# Microcontroleur_Affichage.net
KiCad netlist of a schematic drawn in Altium Designer
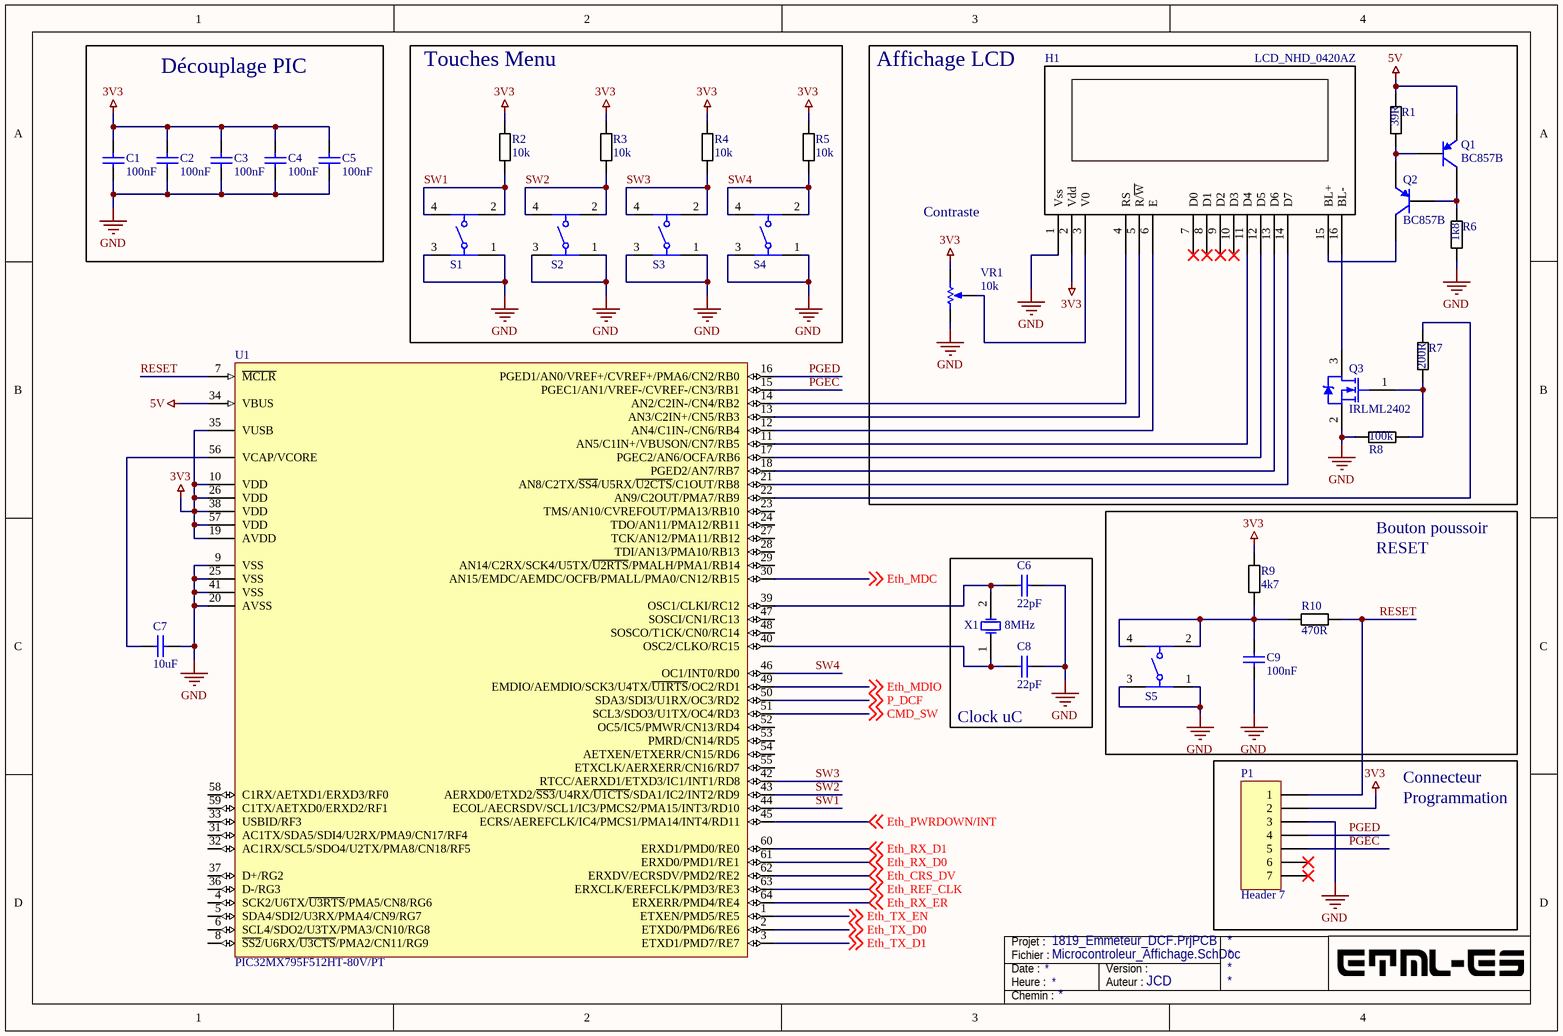
[diagram p0: Microcontroleur_Affichage.SchDoc]

(export (version "E")
  (design (tool "Eeschema 10.0.6"))
  (components
    (comp (ref "C1")
      (value "100nF")
      (footprint "C0805")
      (description "Capacitor")
      (fields (field (name "PUBLISHER") "Altium Limited"))
      (libsource (lib "Miscellaneous Devices") (part "Cap"))
    )
    (comp (ref "C2")
      (value "100nF")
      (footprint "C0805")
      (description "Capacitor")
      (fields (field (name "PUBLISHER") "Altium Limited"))
      (libsource (lib "Miscellaneous Devices") (part "Cap"))
    )
    (comp (ref "C3")
      (value "100nF")
      (footprint "C0805")
      (description "Capacitor")
      (fields (field (name "PUBLISHER") "Altium Limited"))
      (libsource (lib "Miscellaneous Devices") (part "Cap"))
    )
    (comp (ref "C4")
      (value "100nF")
      (footprint "C0805")
      (description "Capacitor")
      (fields (field (name "PUBLISHER") "Altium Limited"))
      (libsource (lib "Miscellaneous Devices") (part "Cap"))
    )
    (comp (ref "C5")
      (value "100nF")
      (footprint "C0805")
      (description "Capacitor")
      (fields (field (name "PUBLISHER") "Altium Limited"))
      (libsource (lib "Miscellaneous Devices") (part "Cap"))
    )
    (comp (ref "C6")
      (value "22pF")
      (footprint "C0805")
      (description "Capacitor")
      (fields (field (name "PUBLISHER") "Altium Limited"))
      (libsource (lib "Miscellaneous Devices") (part "Cap"))
    )
    (comp (ref "C7")
      (value "10uF")
      (footprint "C0805")
      (description "Capacitor")
      (fields (field (name "PUBLISHER") "Altium Limited"))
      (libsource (lib "Miscellaneous Devices") (part "Cap"))
    )
    (comp (ref "C8")
      (value "22pF")
      (footprint "C0805")
      (description "Capacitor")
      (fields (field (name "PUBLISHER") "Altium Limited"))
      (libsource (lib "Miscellaneous Devices") (part "Cap"))
    )
    (comp (ref "C9")
      (value "100nF")
      (footprint "C0805")
      (description "Capacitor")
      (fields (field (name "PUBLISHER") "Altium Limited"))
      (libsource (lib "Miscellaneous Devices") (part "Cap"))
    )
    (comp (ref "H1")
      (value "LCD_NHD_0420AZ")
      (footprint "NHD-0420AZ-FSW-GBW-33V3")
      (libsource (lib "LibComposant1819") (part "NHD-0420AZ-FSW-GBW-33V3"))
    )
    (comp (ref "P1")
      (value "Header 7")
      (footprint "HDR1X7")
      (description "Header, 7-Pin")
      (fields (field (name "PUBLISHER") "Altium Limited"))
      (libsource (lib "Miscellaneous Connectors") (part "Header 7"))
    )
    (comp (ref "Q1")
      (value "BC857B")
      (footprint "INF-SOT23_L")
      (description "PNP Silicon AF Transistor, 45 V VCEO, 100 mA IC, SOT23, Reel, Green")
      (fields (field (name "MANUFACTURER") "Infineon"))
      (libsource (lib "Altium Content Vault") (part "INF-BJTPNP-BEC-3"))
    )
    (comp (ref "Q2")
      (value "BC857B")
      (footprint "INF-SOT23_L")
      (description "PNP Silicon AF Transistor, 45 V VCEO, 100 mA IC, SOT23, Reel, Green")
      (fields (field (name "MANUFACTURER") "Infineon"))
      (libsource (lib "Altium Content Vault") (part "INF-BJTPNP-BEC-3"))
    )
    (comp (ref "Q3")
      (value "IRLML2402")
      (footprint "INTR-IRLML2402TRPBF-3_V")
      (description "HEXFET(R) Power MOSFET, N-Channel, 20 V, 1.2 A, 3-Pin SOT-23, RoHS, Tape and Reel")
      (fields (field (name "MANUFACTURER") "International Rectifier"))
      (libsource (lib "Altium Content Vault") (part "NEMOS-GSD-3_A"))
    )
    (comp (ref "R1") (value "39R") (footprint "RESC0805(2012)_L") (libsource (lib "") (part "Resistance_1")))
    (comp (ref "R2") (value "10k") (footprint "RESC0805(2012)_L") (libsource (lib "") (part "Resistance_2")))
    (comp (ref "R3") (value "10k") (footprint "RESC0805(2012)_L") (libsource (lib "") (part "Resistance_2")))
    (comp (ref "R4") (value "10k") (footprint "RESC0805(2012)_L") (libsource (lib "") (part "Resistance_2")))
    (comp (ref "R5") (value "10k") (footprint "RESC0805(2012)_L") (libsource (lib "") (part "Resistance_2")))
    (comp (ref "R6") (value "1k8") (footprint "RESC0805(2012)_L") (libsource (lib "") (part "Resistance_1")))
    (comp (ref "R7") (value "200R") (footprint "RESC0805(2012)_L") (libsource (lib "") (part "Resistance_1")))
    (comp (ref "R8")
      (value "100k")
      (footprint "RESC0805(2012)_L")
      (libsource (lib "LibComposant1819") (part "Resistance"))
    )
    (comp (ref "R9") (value "4k7") (footprint "RESC0805(2012)_L") (libsource (lib "") (part "Resistance_2")))
    (comp (ref "R10")
      (value "470R")
      (footprint "RESC0805(2012)_L")
      (libsource (lib "LibComposant1819") (part "Resistance"))
    )
    (comp (ref "S1")
      (value "430152095836")
      (footprint "430152095836")
      (description "6x6mm SMD Tact Switch WS-TASV, height 9.5 mm, 360 gf")
      (fields (field (name "PUBLISHER") "Wurth Elektronik"))
      (libsource (lib "ALTIUM-WS-TASV-rev17b") (part "430152095836"))
    )
    (comp (ref "S2")
      (value "430152095836")
      (footprint "430152095836")
      (description "6x6mm SMD Tact Switch WS-TASV, height 9.5 mm, 360 gf")
      (fields (field (name "PUBLISHER") "Wurth Elektronik"))
      (libsource (lib "ALTIUM-WS-TASV-rev17b") (part "430152095836"))
    )
    (comp (ref "S3")
      (value "430152095836")
      (footprint "430152095836")
      (description "6x6mm SMD Tact Switch WS-TASV, height 9.5 mm, 360 gf")
      (fields (field (name "PUBLISHER") "Wurth Elektronik"))
      (libsource (lib "ALTIUM-WS-TASV-rev17b") (part "430152095836"))
    )
    (comp (ref "S4")
      (value "430152095836")
      (footprint "430152095836")
      (description "6x6mm SMD Tact Switch WS-TASV, height 9.5 mm, 360 gf")
      (fields (field (name "PUBLISHER") "Wurth Elektronik"))
      (libsource (lib "ALTIUM-WS-TASV-rev17b") (part "430152095836"))
    )
    (comp (ref "S5")
      (value "430152043836")
      (footprint "430152043836")
      (description "6x6mm SMD Tact Switch WS-TASV, height 4.3 mm, 360 gf")
      (fields (field (name "PUBLISHER") "Wurth Elektronik"))
      (libsource (lib "ALTIUM-WS-TASV-rev17b") (part "430152043836"))
    )
    (comp (ref "U1")
      (value "PIC32MX795F512HT-80V/PT")
      (footprint "TQFP-PT64_L")
      (libsource (lib "Altium Content Vault") (part "MC-32B-MX795-SQ64"))
    )
    (comp (ref "VR1")
      (value "10k")
      (footprint "BOUR-3362P")
      (description "Square Trimpot(R) Trimming Potentiometer, 10 KOhm, 300 V, -55 to 125 degC, 3-Pin THD, RoHS, Tube")
      (fields (field (name "TOLERANCE") "1%"))
      (libsource (lib "Altium Content Vault") (part "RES-POT-3"))
    )
    (comp (ref "X1")
      (value "8MHz")
      (footprint "ECS-80-18-5PX-TR_V")
      (description "Low Profile Quartz Crystal, 8.0 MHz, 2-Pin SMD, RoHS, Tape and Reel")
      (fields (field (name "TOLERANCE") "30PPM") (field (name "MANUFACTURER") "ECS"))
      (libsource (lib "Altium Content Vault") (part "XTAL_1-2-2"))
    )
  )
  (nets
    (net (code "1") (name "/PGEC") (class "Default")
      (node (ref "P1") (pin "5") (pinfunction "5_5") (pintype "passive"))
      (node (ref "U1") (pin "15") (pinfunction "PGEC1/AN1/VREF-/CVREF-/CN3/RB1_15") (pintype "bidirectional"))
    )
    (net (code "2") (name "/PGED") (class "Default")
      (node (ref "P1") (pin "4") (pinfunction "4_4") (pintype "passive"))
      (node (ref "U1") (pin "16") (pinfunction "PGED1/AN0/VREF+/CVREF+/PMA6/CN2/RB0_16") (pintype "bidirectional"))
    )
    (net (code "3") (name "/RESET") (class "Default")
      (node (ref "P1") (pin "1") (pinfunction "1_1") (pintype "passive"))
      (node (ref "R10") (pin "2") (pinfunction "2_2") (pintype "passive"))
      (node (ref "U1") (pin "7") (pinfunction "~{MCLR}_7") (pintype "input"))
    )
    (net (code "4") (name "/SW1") (class "Default")
      (node (ref "R2") (pin "2") (pinfunction "2_2") (pintype "passive"))
      (node (ref "S1") (pin "2") (pinfunction "2_2") (pintype "passive"))
      (node (ref "S1") (pin "4") (pinfunction "4_4") (pintype "passive"))
      (node (ref "U1") (pin "44") (pinfunction "ECOL/AECRSDV/SCL1/IC3/PMCS2/PMA15/INT3/RD10_44") (pintype "bidirectional"))
    )
    (net (code "5") (name "/SW2") (class "Default")
      (node (ref "R3") (pin "2") (pinfunction "2_2") (pintype "passive"))
      (node (ref "S2") (pin "2") (pinfunction "2_2") (pintype "passive"))
      (node (ref "S2") (pin "4") (pinfunction "4_4") (pintype "passive"))
      (node (ref "U1") (pin "43") (pinfunction "AERXD0/ETXD2/~{SS3}/U4RX/~{U1CTS}/SDA1/IC2/INT2/RD9_43") (pintype "bidirectional"))
    )
    (net (code "6") (name "/SW3") (class "Default")
      (node (ref "R4") (pin "2") (pinfunction "2_2") (pintype "passive"))
      (node (ref "S3") (pin "2") (pinfunction "2_2") (pintype "passive"))
      (node (ref "S3") (pin "4") (pinfunction "4_4") (pintype "passive"))
      (node (ref "U1") (pin "42") (pinfunction "RTCC/AERXD1/ETXD3/IC1/INT1/RD8_42") (pintype "bidirectional"))
    )
    (net (code "7") (name "/SW4") (class "Default")
      (node (ref "R5") (pin "2") (pinfunction "2_2") (pintype "passive"))
      (node (ref "S4") (pin "2") (pinfunction "2_2") (pintype "passive"))
      (node (ref "S4") (pin "4") (pinfunction "4_4") (pintype "passive"))
      (node (ref "U1") (pin "46") (pinfunction "OC1/INT0/RD0_46") (pintype "bidirectional"))
    )
    (net (code "8") (name "3V3") (class "Default")
      (node (ref "C1") (pin "2") (pinfunction "2_2") (pintype "passive"))
      (node (ref "C2") (pin "2") (pinfunction "2_2") (pintype "passive"))
      (node (ref "C3") (pin "2") (pinfunction "2_2") (pintype "passive"))
      (node (ref "C4") (pin "2") (pinfunction "2_2") (pintype "passive"))
      (node (ref "C5") (pin "2") (pinfunction "2_2") (pintype "passive"))
      (node (ref "H1") (pin "2") (pinfunction "Vdd_2") (pintype "passive"))
      (node (ref "P1") (pin "2") (pinfunction "2_2") (pintype "passive"))
      (node (ref "R2") (pin "1") (pinfunction "1_1") (pintype "passive"))
      (node (ref "R3") (pin "1") (pinfunction "1_1") (pintype "passive"))
      (node (ref "R4") (pin "1") (pinfunction "1_1") (pintype "passive"))
      (node (ref "R5") (pin "1") (pinfunction "1_1") (pintype "passive"))
      (node (ref "R9") (pin "1") (pinfunction "1_1") (pintype "passive"))
      (node (ref "U1") (pin "10") (pinfunction "VDD_10") (pintype "power_in"))
      (node (ref "U1") (pin "19") (pinfunction "AVDD_19") (pintype "power_in"))
      (node (ref "U1") (pin "26") (pinfunction "VDD_26") (pintype "power_in"))
      (node (ref "U1") (pin "35") (pinfunction "VUSB_35") (pintype "power_in"))
      (node (ref "U1") (pin "38") (pinfunction "VDD_38") (pintype "power_in"))
      (node (ref "U1") (pin "57") (pinfunction "VDD_57") (pintype "power_in"))
      (node (ref "VR1") (pin "3") (pinfunction "CW_3") (pintype "passive"))
    )
    (net (code "9") (name "5V") (class "Default")
      (node (ref "Q1") (pin "2") (pinfunction "E_2") (pintype "passive"))
      (node (ref "R1") (pin "2") (pinfunction "2_2") (pintype "passive"))
      (node (ref "U1") (pin "34") (pinfunction "VBUS_34") (pintype "input"))
    )
    (net (code "10") (name "CMD_SW") (class "Default")
      (node (ref "U1") (pin "51") (pinfunction "SCL3/SDO3/U1TX/OC4/RD3_51") (pintype "bidirectional"))
    )
    (net (code "11") (name "Eth_CRS_DV") (class "Default")
      (node (ref "U1") (pin "62") (pinfunction "ERXDV/ECRSDV/PMD2/RE2_62") (pintype "bidirectional"))
    )
    (net (code "12") (name "Eth_MDC") (class "Default")
      (node (ref "U1") (pin "30") (pinfunction "AN15/EMDC/AEMDC/OCFB/PMALL/PMA0/CN12/RB15_30") (pintype "bidirectional"))
    )
    (net (code "13") (name "Eth_MDIO") (class "Default")
      (node (ref "U1") (pin "49") (pinfunction "EMDIO/AEMDIO/SCK3/U4TX/~{U1RTS}/OC2/RD1_49") (pintype "bidirectional"))
    )
    (net (code "14") (name "Eth_PWRDOWN{slash}INT") (class "Default")
      (node (ref "U1") (pin "45") (pinfunction "ECRS/AEREFCLK/IC4/PMCS1/PMA14/INT4/RD11_45") (pintype "bidirectional"))
    )
    (net (code "15") (name "Eth_REF_CLK") (class "Default")
      (node (ref "U1") (pin "63") (pinfunction "ERXCLK/EREFCLK/PMD3/RE3_63") (pintype "bidirectional"))
    )
    (net (code "16") (name "Eth_RX_D0") (class "Default")
      (node (ref "U1") (pin "61") (pinfunction "ERXD0/PMD1/RE1_61") (pintype "bidirectional"))
    )
    (net (code "17") (name "Eth_RX_D1") (class "Default")
      (node (ref "U1") (pin "60") (pinfunction "ERXD1/PMD0/RE0_60") (pintype "bidirectional"))
    )
    (net (code "18") (name "Eth_RX_ER") (class "Default")
      (node (ref "U1") (pin "64") (pinfunction "ERXERR/PMD4/RE4_64") (pintype "bidirectional"))
    )
    (net (code "19") (name "Eth_TX_D0") (class "Default")
      (node (ref "U1") (pin "2") (pinfunction "ETXD0/PMD6/RE6_2") (pintype "bidirectional"))
    )
    (net (code "20") (name "Eth_TX_D1") (class "Default")
      (node (ref "U1") (pin "3") (pinfunction "ETXD1/PMD7/RE7_3") (pintype "bidirectional"))
    )
    (net (code "21") (name "Eth_TX_EN") (class "Default")
      (node (ref "U1") (pin "1") (pinfunction "ETXEN/PMD5/RE5_1") (pintype "bidirectional"))
    )
    (net (code "22") (name "GND") (class "Default")
      (node (ref "C1") (pin "1") (pinfunction "1_1") (pintype "passive"))
      (node (ref "C2") (pin "1") (pinfunction "1_1") (pintype "passive"))
      (node (ref "C3") (pin "1") (pinfunction "1_1") (pintype "passive"))
      (node (ref "C4") (pin "1") (pinfunction "1_1") (pintype "passive"))
      (node (ref "C5") (pin "1") (pinfunction "1_1") (pintype "passive"))
      (node (ref "C6") (pin "2") (pinfunction "2_2") (pintype "passive"))
      (node (ref "C7") (pin "2") (pinfunction "2_2") (pintype "passive"))
      (node (ref "C8") (pin "2") (pinfunction "2_2") (pintype "passive"))
      (node (ref "C9") (pin "1") (pinfunction "1_1") (pintype "passive"))
      (node (ref "H1") (pin "1") (pinfunction "Vss_1") (pintype "passive"))
      (node (ref "P1") (pin "3") (pinfunction "3_3") (pintype "passive"))
      (node (ref "Q3") (pin "2") (pinfunction "S_2") (pintype "passive"))
      (node (ref "R6") (pin "1") (pinfunction "1_1") (pintype "passive"))
      (node (ref "R8") (pin "1") (pinfunction "1_1") (pintype "passive"))
      (node (ref "S1") (pin "1") (pinfunction "1_1") (pintype "passive"))
      (node (ref "S1") (pin "3") (pinfunction "3_3") (pintype "passive"))
      (node (ref "S2") (pin "1") (pinfunction "1_1") (pintype "passive"))
      (node (ref "S2") (pin "3") (pinfunction "3_3") (pintype "passive"))
      (node (ref "S3") (pin "1") (pinfunction "1_1") (pintype "passive"))
      (node (ref "S3") (pin "3") (pinfunction "3_3") (pintype "passive"))
      (node (ref "S4") (pin "1") (pinfunction "1_1") (pintype "passive"))
      (node (ref "S4") (pin "3") (pinfunction "3_3") (pintype "passive"))
      (node (ref "S5") (pin "1") (pinfunction "1_1") (pintype "passive"))
      (node (ref "S5") (pin "3") (pinfunction "3_3") (pintype "passive"))
      (node (ref "U1") (pin "20") (pinfunction "AVSS_20") (pintype "power_in"))
      (node (ref "U1") (pin "25") (pinfunction "VSS_25") (pintype "power_in"))
      (node (ref "U1") (pin "41") (pinfunction "VSS_41") (pintype "power_in"))
      (node (ref "U1") (pin "9") (pinfunction "VSS_9") (pintype "power_in"))
      (node (ref "VR1") (pin "1") (pinfunction "CCW_1") (pintype "passive"))
    )
    (net (code "23") (name "Net-(C9-Pad2)") (class "Default")
      (node (ref "C9") (pin "2") (pinfunction "2_2") (pintype "passive"))
      (node (ref "R10") (pin "1") (pinfunction "1_1") (pintype "passive"))
      (node (ref "R9") (pin "2") (pinfunction "2_2") (pintype "passive"))
      (node (ref "S5") (pin "2") (pinfunction "2_2") (pintype "passive"))
      (node (ref "S5") (pin "4") (pinfunction "4_4") (pintype "passive"))
    )
    (net (code "24") (name "Net-(H1-BL+)") (class "Default")
      (node (ref "H1") (pin "15") (pinfunction "BL+_15") (pintype "passive"))
      (node (ref "Q2") (pin "3") (pinfunction "C_3") (pintype "passive"))
    )
    (net (code "25") (name "Net-(H1-BL-)") (class "Default")
      (node (ref "H1") (pin "16") (pinfunction "BL-_16") (pintype "passive"))
      (node (ref "Q3") (pin "3") (pinfunction "D_3") (pintype "passive"))
    )
    (net (code "26") (name "Net-(H1-D4)") (class "Default")
      (node (ref "H1") (pin "11") (pinfunction "D4_11") (pintype "passive"))
      (node (ref "U1") (pin "11") (pinfunction "AN5/C1IN+/VBUSON/CN7/RB5_11") (pintype "bidirectional"))
    )
    (net (code "27") (name "Net-(H1-D5)") (class "Default")
      (node (ref "H1") (pin "12") (pinfunction "D5_12") (pintype "passive"))
      (node (ref "U1") (pin "17") (pinfunction "PGEC2/AN6/OCFA/RB6_17") (pintype "bidirectional"))
    )
    (net (code "28") (name "Net-(H1-D6)") (class "Default")
      (node (ref "H1") (pin "13") (pinfunction "D6_13") (pintype "passive"))
      (node (ref "U1") (pin "18") (pinfunction "PGED2/AN7/RB7_18") (pintype "bidirectional"))
    )
    (net (code "29") (name "Net-(H1-D7)") (class "Default")
      (node (ref "H1") (pin "14") (pinfunction "D7_14") (pintype "passive"))
      (node (ref "U1") (pin "21") (pinfunction "AN8/C2TX/~{SS4}/U5RX/~{U2CTS}/C1OUT/RB8_21") (pintype "bidirectional"))
    )
    (net (code "30") (name "Net-(H1-E)") (class "Default")
      (node (ref "H1") (pin "6") (pinfunction "E_6") (pintype "passive"))
      (node (ref "U1") (pin "12") (pinfunction "AN4/C1IN-/CN6/RB4_12") (pintype "bidirectional"))
    )
    (net (code "31") (name "Net-(H1-RS)") (class "Default")
      (node (ref "H1") (pin "4") (pinfunction "RS_4") (pintype "passive"))
      (node (ref "U1") (pin "14") (pinfunction "AN2/C2IN-/CN4/RB2_14") (pintype "bidirectional"))
    )
    (net (code "32") (name "Net-(H1-R{slash}~{W})") (class "Default")
      (node (ref "H1") (pin "5") (pinfunction "R/~{W}_5") (pintype "passive"))
      (node (ref "U1") (pin "13") (pinfunction "AN3/C2IN+/CN5/RB3_13") (pintype "bidirectional"))
    )
    (net (code "33") (name "Net-(H1-V0)") (class "Default")
      (node (ref "H1") (pin "3") (pinfunction "V0_3") (pintype "passive"))
      (node (ref "VR1") (pin "2") (pinfunction "S_2") (pintype "passive"))
    )
    (net (code "34") (name "Net-(Q1-B)") (class "Default")
      (node (ref "Q1") (pin "1") (pinfunction "B_1") (pintype "passive"))
      (node (ref "Q2") (pin "2") (pinfunction "E_2") (pintype "passive"))
      (node (ref "R1") (pin "1") (pinfunction "1_1") (pintype "passive"))
    )
    (net (code "35") (name "Net-(Q1-C)") (class "Default")
      (node (ref "Q1") (pin "3") (pinfunction "C_3") (pintype "passive"))
      (node (ref "Q2") (pin "1") (pinfunction "B_1") (pintype "passive"))
      (node (ref "R6") (pin "2") (pinfunction "2_2") (pintype "passive"))
    )
    (net (code "36") (name "Net-(Q3-G)") (class "Default")
      (node (ref "Q3") (pin "1") (pinfunction "G_1") (pintype "passive"))
      (node (ref "R7") (pin "1") (pinfunction "1_1") (pintype "passive"))
      (node (ref "R8") (pin "2") (pinfunction "2_2") (pintype "passive"))
    )
    (net (code "37") (name "Net-(U1-AN9{slash}C2OUT{slash}PMA7{slash}RB9)") (class "Default")
      (node (ref "R7") (pin "2") (pinfunction "2_2") (pintype "passive"))
      (node (ref "U1") (pin "22") (pinfunction "AN9/C2OUT/PMA7/RB9_22") (pintype "bidirectional"))
    )
    (net (code "38") (name "Net-(U1-OSC1{slash}CLKI{slash}RC12)") (class "Default")
      (node (ref "C6") (pin "1") (pinfunction "1_1") (pintype "passive"))
      (node (ref "U1") (pin "39") (pinfunction "OSC1/CLKI/RC12_39") (pintype "bidirectional"))
      (node (ref "X1") (pin "2") (pinfunction "X2_2") (pintype "passive"))
    )
    (net (code "39") (name "Net-(U1-OSC2{slash}CLKO{slash}RC15)") (class "Default")
      (node (ref "C8") (pin "1") (pinfunction "1_1") (pintype "passive"))
      (node (ref "U1") (pin "40") (pinfunction "OSC2/CLKO/RC15_40") (pintype "bidirectional"))
      (node (ref "X1") (pin "1") (pinfunction "X1_1") (pintype "passive"))
    )
    (net (code "40") (name "Net-(U1-VCAP{slash}VCORE)") (class "Default")
      (node (ref "C7") (pin "1") (pinfunction "1_1") (pintype "passive"))
      (node (ref "U1") (pin "56") (pinfunction "VCAP/VCORE_56") (pintype "power_in"))
    )
    (net (code "41") (name "P_DCF") (class "Default")
      (node (ref "U1") (pin "50") (pinfunction "SDA3/SDI3/U1RX/OC3/RD2_50") (pintype "bidirectional"))
    )
    (net (code "42") (name "unconnected-(H1-D0-Pad7)") (class "Default")
      (node (ref "H1") (pin "7") (pinfunction "D0_7") (pintype "passive+no_connect"))
    )
    (net (code "43") (name "unconnected-(H1-D1-Pad8)") (class "Default")
      (node (ref "H1") (pin "8") (pinfunction "D1_8") (pintype "passive+no_connect"))
    )
    (net (code "44") (name "unconnected-(H1-D2-Pad9)") (class "Default")
      (node (ref "H1") (pin "9") (pinfunction "D2_9") (pintype "passive+no_connect"))
    )
    (net (code "45") (name "unconnected-(H1-D3-Pad10)") (class "Default")
      (node (ref "H1") (pin "10") (pinfunction "D3_10") (pintype "passive+no_connect"))
    )
    (net (code "46") (name "unconnected-(P1-Pad6)") (class "Default")
      (node (ref "P1") (pin "6") (pinfunction "6_6") (pintype "passive+no_connect"))
    )
    (net (code "47") (name "unconnected-(P1-Pad7)") (class "Default")
      (node (ref "P1") (pin "7") (pinfunction "7_7") (pintype "passive+no_connect"))
    )
    (net (code "48") (name "unconnected-(U1-AC1RX{slash}SCL5{slash}SDO4{slash}U2TX{slash}PMA8{slash}CN18{slash}RF5-Pad32)") (class "Default")
      (node (ref "U1") (pin "32") (pinfunction "AC1RX/SCL5/SDO4/U2TX/PMA8/CN18/RF5_32") (pintype "bidirectional"))
    )
    (net (code "49") (name "unconnected-(U1-AC1TX{slash}SDA5{slash}SDI4{slash}U2RX{slash}PMA9{slash}CN17{slash}RF4-Pad31)") (class "Default")
      (node (ref "U1") (pin "31") (pinfunction "AC1TX/SDA5/SDI4/U2RX/PMA9/CN17/RF4_31") (pintype "bidirectional"))
    )
    (net (code "50") (name "unconnected-(U1-AETXEN{slash}ETXERR{slash}CN15{slash}RD6-Pad54)") (class "Default")
      (node (ref "U1") (pin "54") (pinfunction "AETXEN/ETXERR/CN15/RD6_54") (pintype "bidirectional"))
    )
    (net (code "51") (name "unconnected-(U1-AN14{slash}C2RX{slash}SCK4{slash}U5TX{slash}~{U2RTS}{slash}PMALH{slash}PMA1{slash}RB14-Pad29)") (class "Default")
      (node (ref "U1") (pin "29") (pinfunction "AN14/C2RX/SCK4/U5TX/~{U2RTS}/PMALH/PMA1/RB14_29") (pintype "bidirectional"))
    )
    (net (code "52") (name "unconnected-(U1-C1RX{slash}AETXD1{slash}ERXD3{slash}RF0-Pad58)") (class "Default")
      (node (ref "U1") (pin "58") (pinfunction "C1RX/AETXD1/ERXD3/RF0_58") (pintype "bidirectional"))
    )
    (net (code "53") (name "unconnected-(U1-C1TX{slash}AETXD0{slash}ERXD2{slash}RF1-Pad59)") (class "Default")
      (node (ref "U1") (pin "59") (pinfunction "C1TX/AETXD0/ERXD2/RF1_59") (pintype "bidirectional"))
    )
    (net (code "54") (name "unconnected-(U1-D+{slash}RG2-Pad37)") (class "Default")
      (node (ref "U1") (pin "37") (pinfunction "D+/RG2_37") (pintype "bidirectional"))
    )
    (net (code "55") (name "unconnected-(U1-D-{slash}RG3-Pad36)") (class "Default")
      (node (ref "U1") (pin "36") (pinfunction "D-/RG3_36") (pintype "bidirectional"))
    )
    (net (code "56") (name "unconnected-(U1-ETXCLK{slash}AERXERR{slash}CN16{slash}RD7-Pad55)") (class "Default")
      (node (ref "U1") (pin "55") (pinfunction "ETXCLK/AERXERR/CN16/RD7_55") (pintype "bidirectional"))
    )
    (net (code "57") (name "unconnected-(U1-OC5{slash}IC5{slash}PMWR{slash}CN13{slash}RD4-Pad52)") (class "Default")
      (node (ref "U1") (pin "52") (pinfunction "OC5/IC5/PMWR/CN13/RD4_52") (pintype "bidirectional"))
    )
    (net (code "58") (name "unconnected-(U1-PMRD{slash}CN14{slash}RD5-Pad53)") (class "Default")
      (node (ref "U1") (pin "53") (pinfunction "PMRD/CN14/RD5_53") (pintype "bidirectional"))
    )
    (net (code "59") (name "unconnected-(U1-SCK2{slash}U6TX{slash}~{U3RTS}{slash}PMA5{slash}CN8{slash}RG6-Pad4)") (class "Default")
      (node (ref "U1") (pin "4") (pinfunction "SCK2/U6TX/~{U3RTS}/PMA5/CN8/RG6_4") (pintype "bidirectional"))
    )
    (net (code "60") (name "unconnected-(U1-SCL4{slash}SDO2{slash}U3TX{slash}PMA3{slash}CN10{slash}RG8-Pad6)") (class "Default")
      (node (ref "U1") (pin "6") (pinfunction "SCL4/SDO2/U3TX/PMA3/CN10/RG8_6") (pintype "bidirectional"))
    )
    (net (code "61") (name "unconnected-(U1-SDA4{slash}SDI2{slash}U3RX{slash}PMA4{slash}CN9{slash}RG7-Pad5)") (class "Default")
      (node (ref "U1") (pin "5") (pinfunction "SDA4/SDI2/U3RX/PMA4/CN9/RG7_5") (pintype "bidirectional"))
    )
    (net (code "62") (name "unconnected-(U1-SOSCI{slash}CN1{slash}RC13-Pad47)") (class "Default")
      (node (ref "U1") (pin "47") (pinfunction "SOSCI/CN1/RC13_47") (pintype "bidirectional"))
    )
    (net (code "63") (name "unconnected-(U1-SOSCO{slash}T1CK{slash}CN0{slash}RC14-Pad48)") (class "Default")
      (node (ref "U1") (pin "48") (pinfunction "SOSCO/T1CK/CN0/RC14_48") (pintype "bidirectional"))
    )
    (net (code "64") (name "unconnected-(U1-TCK{slash}AN12{slash}PMA11{slash}RB12-Pad27)") (class "Default")
      (node (ref "U1") (pin "27") (pinfunction "TCK/AN12/PMA11/RB12_27") (pintype "bidirectional"))
    )
    (net (code "65") (name "unconnected-(U1-TDI{slash}AN13{slash}PMA10{slash}RB13-Pad28)") (class "Default")
      (node (ref "U1") (pin "28") (pinfunction "TDI/AN13/PMA10/RB13_28") (pintype "bidirectional"))
    )
    (net (code "66") (name "unconnected-(U1-TDO{slash}AN11{slash}PMA12{slash}RB11-Pad24)") (class "Default")
      (node (ref "U1") (pin "24") (pinfunction "TDO/AN11/PMA12/RB11_24") (pintype "bidirectional"))
    )
    (net (code "67") (name "unconnected-(U1-TMS{slash}AN10{slash}CVREFOUT{slash}PMA13{slash}RB10-Pad23)") (class "Default")
      (node (ref "U1") (pin "23") (pinfunction "TMS/AN10/CVREFOUT/PMA13/RB10_23") (pintype "bidirectional"))
    )
    (net (code "68") (name "unconnected-(U1-USBID{slash}RF3-Pad33)") (class "Default")
      (node (ref "U1") (pin "33") (pinfunction "USBID/RF3_33") (pintype "bidirectional"))
    )
    (net (code "69") (name "unconnected-(U1-~{SS2}{slash}U6RX{slash}~{U3CTS}{slash}PMA2{slash}CN11{slash}RG9-Pad8)") (class "Default")
      (node (ref "U1") (pin "8") (pinfunction "~{SS2}/U6RX/~{U3CTS}/PMA2/CN11/RG9_8") (pintype "bidirectional"))
    )
  )
)
